# Top.net
KiCad netlist of a schematic drawn in Altium Designer
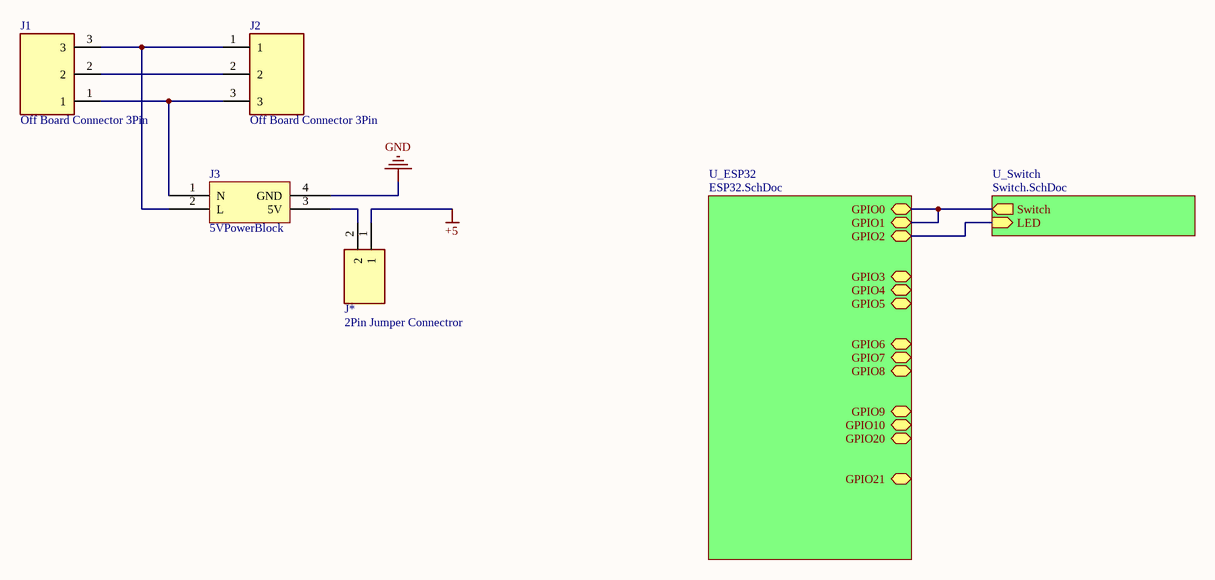
[diagram p0: Top.SchDoc]

(export (version "E")
  (design (tool "Eeschema 10.0.6"))
  (components
    (comp (ref "J*")
      (value "2Pin Jumper Connectror")
      (footprint "2Pin Jumper")
      (libsource (lib "OST") (part "2Pin Jumper"))
    )
    (comp (ref "J1")
      (value "Off Board Connector 3Pin")
      (footprint "OFF BORAD CONNECTOR 3PIN")
      (description "Screw Connector")
      (libsource (lib "") (part "Off Board Connector 3Pin_1"))
    )
    (comp (ref "J2")
      (value "Off Board Connector 3Pin")
      (footprint "OFF BORAD CONNECTOR 3PIN")
      (description "Screw Connector")
      (libsource (lib "OST") (part "Off Board Connector 3Pin"))
    )
    (comp (ref "J3")
      (value "5VPowerBlock")
      (footprint "5VPowerBlock")
      (libsource (lib "OST") (part "5VPowerBlock"))
    )
  )
  (nets
    (net (code "1") (name "+5") (class "Default")
      (node (ref "J*") (pin "1") (pinfunction "1_1") (pintype "passive"))
    )
    (net (code "14") (name "GND") (class "Default")
      (node (ref "J3") (pin "4") (pinfunction "GND_4") (pintype "power_in"))
    )
    (net (code "15") (name "Net-(J1-Pad2)") (class "Default")
      (node (ref "J1") (pin "2") (pinfunction "2_2") (pintype "passive"))
      (node (ref "J2") (pin "2") (pinfunction "2_2") (pintype "passive"))
    )
    (net (code "16") (name "Net-(J3-5V)") (class "Default")
      (node (ref "J*") (pin "2") (pinfunction "2_2") (pintype "passive"))
      (node (ref "J3") (pin "3") (pinfunction "5V_3") (pintype "power_in"))
    )
    (net (code "17") (name "Net-(J3-L)") (class "Default")
      (node (ref "J1") (pin "3") (pinfunction "3_3") (pintype "passive"))
      (node (ref "J2") (pin "1") (pinfunction "1_1") (pintype "passive"))
      (node (ref "J3") (pin "2") (pinfunction "L_2") (pintype "power_in"))
    )
    (net (code "18") (name "Net-(J3-N)") (class "Default")
      (node (ref "J1") (pin "1") (pinfunction "1_1") (pintype "passive"))
      (node (ref "J2") (pin "3") (pinfunction "3_3") (pintype "passive"))
      (node (ref "J3") (pin "1") (pinfunction "N_1") (pintype "power_in"))
    )
  )
)
